# Sheet2.net
KiCad netlist of a schematic drawn in Altium Designer
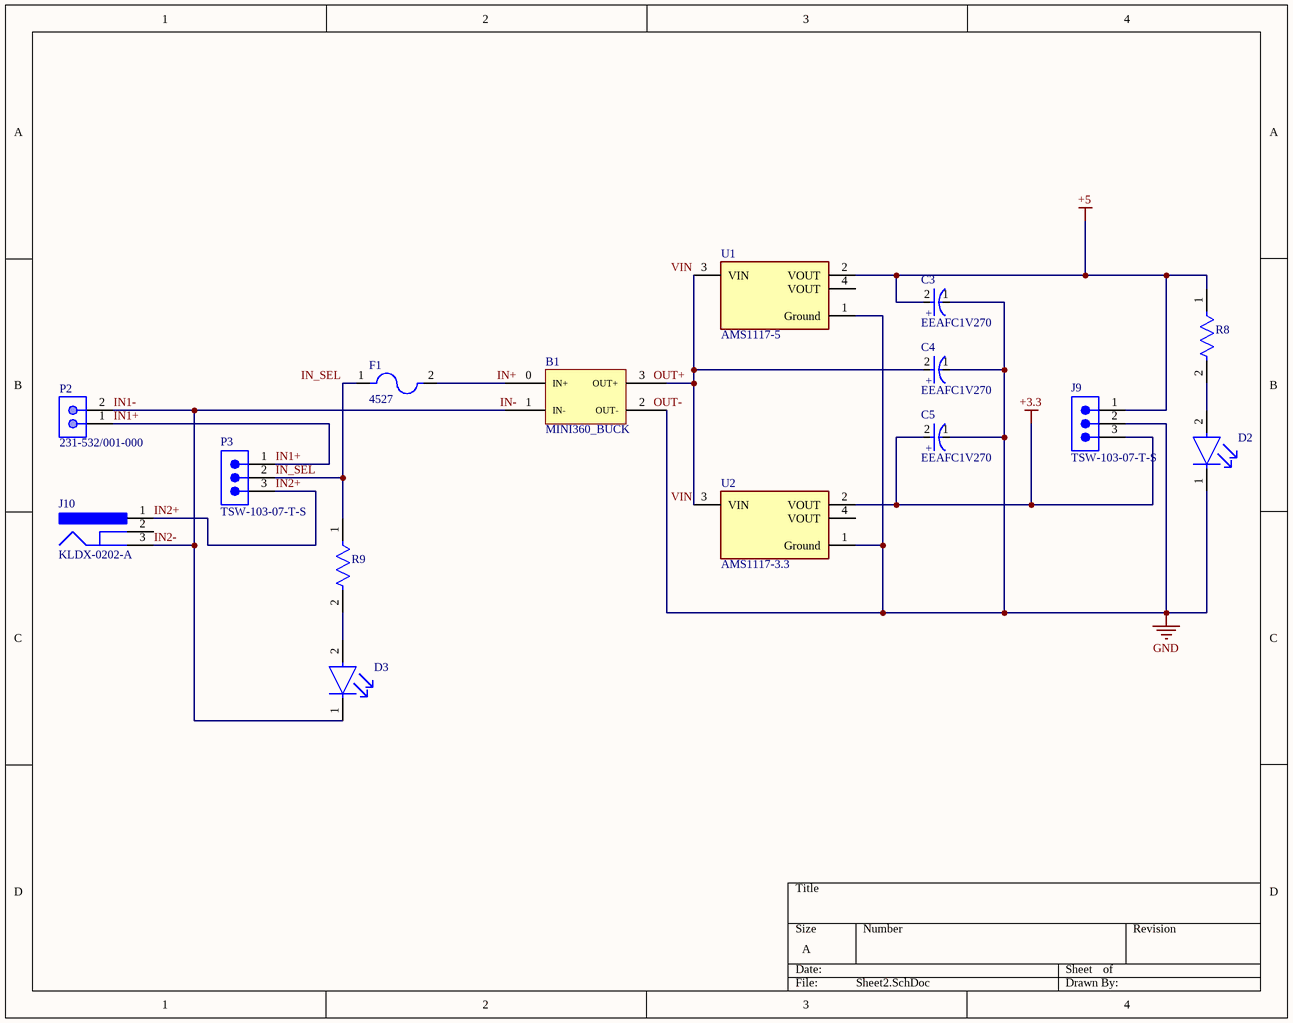
[diagram p0: Sheet2.SchDoc]

(export (version "E")
  (design (tool "Eeschema 10.0.6"))
  (components
    (comp (ref "B1")
      (value "MINI360_BUCK")
      (footprint "MINI360_BUCK")
      (libsource (lib "MyComponents") (part "MINI360_BUCK"))
    )
    (comp (ref "C3")
      (value "EEAFC1V270")
      (footprint "FP-RAD-TH-D_6_3_0_5-L_7_1-MFG")
      (description "Aluminum Electrolytic Capacitors (Radial Lead Type) AEC-Q200 Qualified 27uF ±20% 35V")
      (fields (field (name "TOLERANCE") "20%") (field (name "VOLTAGE") "35V"))
      (libsource (lib "Altium Content Vault") (part "a00bbbee19879c290e62620ae7e47b1"))
    )
    (comp (ref "C4")
      (value "EEAFC1V270")
      (footprint "FP-RAD-TH-D_6_3_0_5-L_7_1-MFG")
      (description "Aluminum Electrolytic Capacitors (Radial Lead Type) AEC-Q200 Qualified 27uF ±20% 35V")
      (fields (field (name "TOLERANCE") "20%") (field (name "VOLTAGE") "35V"))
      (libsource (lib "Altium Content Vault") (part "a00bbbee19879c290e62620ae7e47b1"))
    )
    (comp (ref "C5")
      (value "EEAFC1V270")
      (footprint "FP-RAD-TH-D_6_3_0_5-L_7_1-MFG")
      (description "Aluminum Electrolytic Capacitors (Radial Lead Type) AEC-Q200 Qualified 27uF ±20% 35V")
      (fields (field (name "TOLERANCE") "20%") (field (name "VOLTAGE") "35V"))
      (libsource (lib "Altium Content Vault") (part "a00bbbee19879c290e62620ae7e47b1"))
    )
    (comp (ref "D2")
      (value "SSL-LX5093YD")
      (footprint "FP-SSL-LX5093YD-MFG")
      (description "LED YELLOW DIFFUSED T-1 3/4 T/H")
      (libsource (lib "Altium Content Vault") (part "8706943c75ba83719d021d2fdc84c58"))
    )
    (comp (ref "D3")
      (value "SSL-LX5093YD")
      (footprint "FP-SSL-LX5093YD-MFG")
      (description "LED YELLOW DIFFUSED T-1 3/4 T/H")
      (libsource (lib "Altium Content Vault") (part "8706943c75ba83719d021d2fdc84c58"))
    )
    (comp (ref "F1")
      (value "4527")
      (footprint "FUSE_4527")
      (description "5mm Low Profile Holder")
      (fields (field (name "MF") "Keystone"))
      (libsource (lib "MyComponents") (part "4527"))
    )
    (comp (ref "J9")
      (value "TSW-103-07-T-S")
      (footprint "SMTC-TSW-103-07-X-S")
      (description "0.025\" SQ Post Header, Through-hole, Vertical, -55 to 105 degC, 2.54 mm Pitch, 3-Pin, Male, RoHS")
      (fields (field (name "MANUFACTURER") "Samtec"))
      (libsource (lib "Altium Content Vault") (part "SMTC-TSW-103-X-X-S-X"))
    )
    (comp (ref "J10")
      (value "KLDX-0202-A")
      (footprint "KYCN-KLDX-0202-A_V")
      (description "DC Power Jack, 24 V, 3.5 A, -25 to 85 degC, 3-Pin THD, RoHS")
      (fields (field (name "MANUFACTURER") "Kycon"))
      (libsource (lib "Altium Content Vault") (part "JACK-2CD3-RN"))
    )
    (comp (ref "P2")
      (value "231-532/001-000")
      (footprint "WAGO-231-532-001-000_V")
      (description "Male Connector, Right Angle, Pitch 5.08 mm, 1 x 2 Posistion, Height 8.4 mm, -60 to 100 degC, RoHS")
      (fields (field (name "MANUFACTURER") "WAGO"))
      (libsource (lib "Altium Content Vault") (part "CN-1P-M-R2"))
    )
    (comp (ref "P3")
      (value "TSW-103-07-T-S")
      (footprint "SMTC-TSW-103-07-X-S")
      (description "0.025\" SQ Post Header, Through-hole, Vertical, -55 to 105 degC, 2.54 mm Pitch, 3-Pin, Male, RoHS")
      (fields (field (name "MANUFACTURER") "Samtec"))
      (libsource (lib "Altium Content Vault") (part "SMTC-TSW-103-X-X-S-X"))
    )
    (comp (ref "R8")
      (value "VR37000001204JA100")
      (footprint "FP-VR37-MFG")
      (description "RES 1.2M OHM 5% 1/2W AXIAL")
      (fields (field (name "TOLERANCE") "5%"))
      (libsource (lib "Altium Content Vault") (part "1029c3af85768c4190bb7ad29bc67b5"))
    )
    (comp (ref "R9")
      (value "VR37000001204JA100")
      (footprint "FP-VR37-MFG")
      (description "RES 1.2M OHM 5% 1/2W AXIAL")
      (fields (field (name "TOLERANCE") "5%"))
      (libsource (lib "Altium Content Vault") (part "1029c3af85768c4190bb7ad29bc67b5"))
    )
    (comp (ref "U1")
      (value "AMS1117-5")
      (footprint "FP-AMS1117-IPC_C")
      (description "LDO Voltage Regulators 1A, 3.3V")
      (fields
        (field (name "MANUFACTURER PART NUMBER") "AMS1117-3.3")
        (field (name "OCTOPART") "https://octopart.com/ams1117-3.3-advanced+monolithic+systems-25899300")
      )
      (libsource (lib "Altium Content Vault") (part "8bdbb5f8e77002000e30dd2845d0354"))
    )
    (comp (ref "U2")
      (value "AMS1117-3.3")
      (footprint "FP-AMS1117-IPC_C")
      (description "LDO Voltage Regulators 1A, 3.3V")
      (fields
        (field (name "OCTOPART") "https://octopart.com/ams1117-3.3-advanced+monolithic+systems-25899300")
        (field (name "MANUFACTURER") "Advanced Monolithic Systems")
      )
      (libsource (lib "Altium Content Vault") (part "8bdbb5f8e77002000e30dd2845d0354"))
    )
  )
  (nets
    (net (code "1") (name "+3.3") (class "Default")
      (node (ref "C5") (pin "2") (pinfunction "A_2") (pintype "passive"))
      (node (ref "J9") (pin "3") (pinfunction "3_3") (pintype "passive"))
      (node (ref "U2") (pin "2") (pinfunction "VOUT_2") (pintype "passive"))
    )
    (net (code "2") (name "+5") (class "Default")
      (node (ref "C3") (pin "2") (pinfunction "A_2") (pintype "passive"))
      (node (ref "J9") (pin "1") (pinfunction "1_1") (pintype "passive"))
      (node (ref "R8") (pin "1") (pinfunction "1_1") (pintype "passive"))
      (node (ref "U1") (pin "2") (pinfunction "VOUT_2") (pintype "passive"))
    )
    (net (code "5") (name "/IN1+") (class "Default")
      (node (ref "P2") (pin "1") (pinfunction "1_1") (pintype "passive"))
      (node (ref "P3") (pin "1") (pinfunction "1_1") (pintype "passive"))
    )
    (net (code "6") (name "/IN1-") (class "Default")
      (node (ref "B1") (pin "1") (pinfunction "IN-_1") (pintype "passive"))
      (node (ref "D3") (pin "1") (pinfunction "C_1") (pintype "passive"))
      (node (ref "J10") (pin "3") (pinfunction "3_3") (pintype "passive"))
      (node (ref "P2") (pin "2") (pinfunction "2_2") (pintype "passive"))
    )
    (net (code "7") (name "/IN2+") (class "Default")
      (node (ref "J10") (pin "1") (pinfunction "1_1") (pintype "passive"))
      (node (ref "P3") (pin "3") (pinfunction "3_3") (pintype "passive"))
    )
    (net (code "8") (name "/IN_SEL") (class "Default")
      (node (ref "F1") (pin "1") (pinfunction "1_1") (pintype "passive"))
      (node (ref "P3") (pin "2") (pinfunction "2_2") (pintype "passive"))
      (node (ref "R9") (pin "1") (pinfunction "1_1") (pintype "passive"))
    )
    (net (code "11") (name "/VIN") (class "Default")
      (node (ref "B1") (pin "3") (pinfunction "OUT+_3") (pintype "passive"))
      (node (ref "C4") (pin "2") (pinfunction "A_2") (pintype "passive"))
      (node (ref "U1") (pin "3") (pinfunction "VIN_3") (pintype "power_in"))
      (node (ref "U2") (pin "3") (pinfunction "VIN_3") (pintype "power_in"))
    )
    (net (code "12") (name "GND") (class "Default")
      (node (ref "B1") (pin "2") (pinfunction "OUT-_2") (pintype "passive"))
      (node (ref "C3") (pin "1") (pinfunction "C_1") (pintype "passive"))
      (node (ref "C4") (pin "1") (pinfunction "C_1") (pintype "passive"))
      (node (ref "C5") (pin "1") (pinfunction "C_1") (pintype "passive"))
      (node (ref "D2") (pin "1") (pinfunction "C_1") (pintype "passive"))
      (node (ref "J9") (pin "2") (pinfunction "2_2") (pintype "passive"))
      (node (ref "U1") (pin "1") (pinfunction "Ground_1") (pintype "power_in"))
      (node (ref "U2") (pin "1") (pinfunction "Ground_1") (pintype "power_in"))
    )
    (net (code "13") (name "Net-(B1-IN+)") (class "Default")
      (node (ref "B1") (pin "0") (pinfunction "IN+_0") (pintype "passive"))
      (node (ref "F1") (pin "2") (pinfunction "2_2") (pintype "passive"))
    )
    (net (code "14") (name "Net-(D2-A)") (class "Default")
      (node (ref "D2") (pin "2") (pinfunction "A_2") (pintype "passive"))
      (node (ref "R8") (pin "2") (pinfunction "2_2") (pintype "passive"))
    )
    (net (code "15") (name "Net-(D3-A)") (class "Default")
      (node (ref "D3") (pin "2") (pinfunction "A_2") (pintype "passive"))
      (node (ref "R9") (pin "2") (pinfunction "2_2") (pintype "passive"))
    )
    (net (code "16") (name "unconnected-(J10-Pad2)") (class "Default")
      (node (ref "J10") (pin "2") (pinfunction "2_2") (pintype "passive"))
    )
    (net (code "17") (name "unconnected-(U1-VOUT-Pad4)") (class "Default")
      (node (ref "U1") (pin "4") (pinfunction "VOUT_4") (pintype "passive"))
    )
    (net (code "18") (name "unconnected-(U2-VOUT-Pad4)") (class "Default")
      (node (ref "U2") (pin "4") (pinfunction "VOUT_4") (pintype "passive"))
    )
  )
)
